# RPi_Extension_contr_sens_conn_board.net
KiCad netlist of a schematic drawn in EAGLE
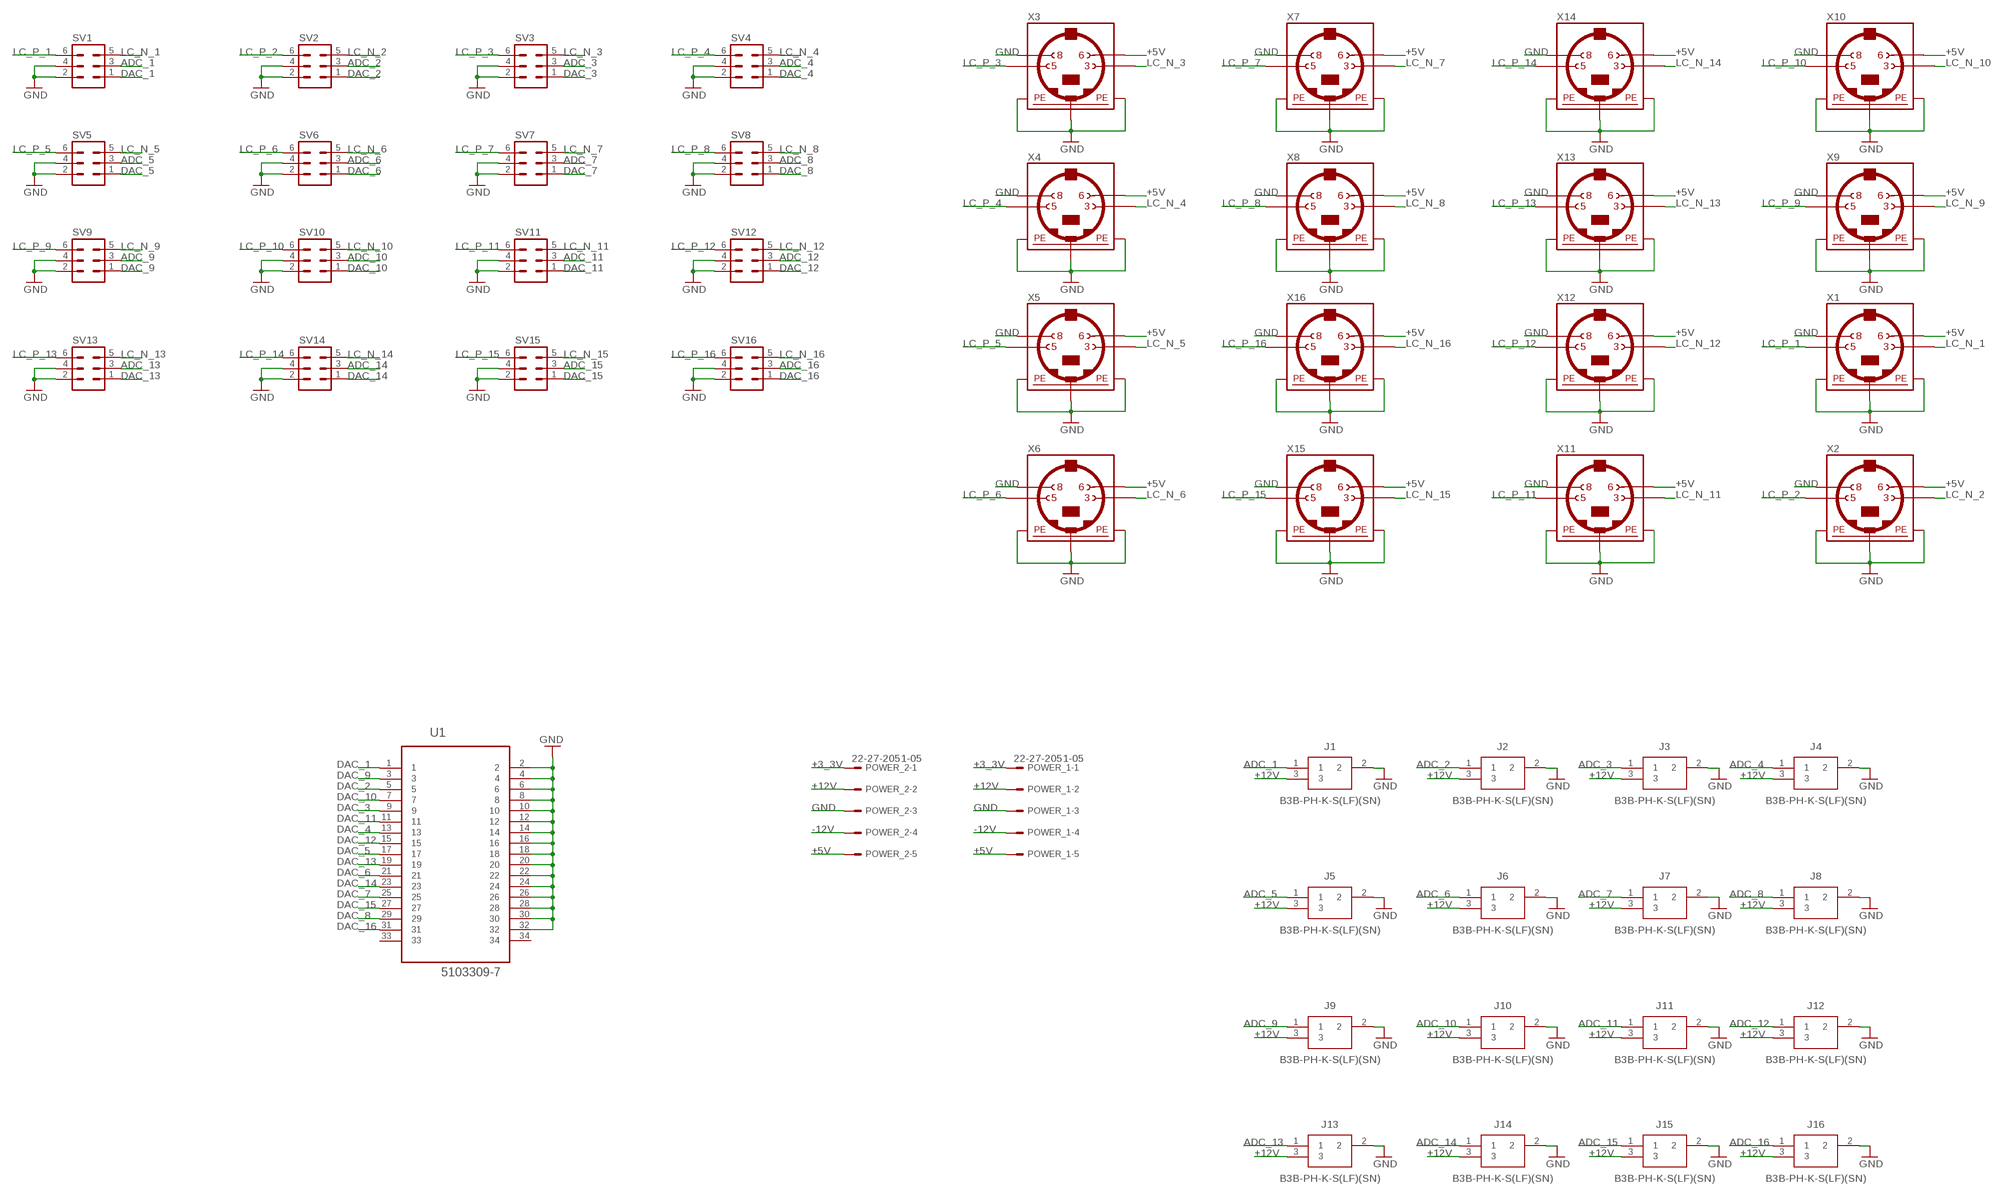
[diagram p0: schematic, sheet 1]

(export (version "E")
  (design (tool "Eeschema 10.0.6"))
  (components
    (comp (ref "J1")
      (value "B3B-PH-K-S(LF)(SN)")
      (footprint "eagle-import:SHDR3W50P0X200_1X3_790X450X600")
      (fields (field (name "RS_PART_NUMBER") "8201431P"))
      (libsource (lib "eagle-import") (part "B3B-PH-K-S(LF)(SN)"))
    )
    (comp (ref "J2")
      (value "B3B-PH-K-S(LF)(SN)")
      (footprint "eagle-import:SHDR3W50P0X200_1X3_790X450X600")
      (fields (field (name "RS_PART_NUMBER") "8201431P"))
      (libsource (lib "eagle-import") (part "B3B-PH-K-S(LF)(SN)"))
    )
    (comp (ref "J3")
      (value "B3B-PH-K-S(LF)(SN)")
      (footprint "eagle-import:SHDR3W50P0X200_1X3_790X450X600")
      (fields (field (name "RS_PART_NUMBER") "8201431P"))
      (libsource (lib "eagle-import") (part "B3B-PH-K-S(LF)(SN)"))
    )
    (comp (ref "J4")
      (value "B3B-PH-K-S(LF)(SN)")
      (footprint "eagle-import:SHDR3W50P0X200_1X3_790X450X600")
      (fields (field (name "RS_PART_NUMBER") "8201431P"))
      (libsource (lib "eagle-import") (part "B3B-PH-K-S(LF)(SN)"))
    )
    (comp (ref "J5")
      (value "B3B-PH-K-S(LF)(SN)")
      (footprint "eagle-import:SHDR3W50P0X200_1X3_790X450X600")
      (fields (field (name "RS_PART_NUMBER") "8201431P"))
      (libsource (lib "eagle-import") (part "B3B-PH-K-S(LF)(SN)"))
    )
    (comp (ref "J6")
      (value "B3B-PH-K-S(LF)(SN)")
      (footprint "eagle-import:SHDR3W50P0X200_1X3_790X450X600")
      (fields (field (name "RS_PART_NUMBER") "8201431P"))
      (libsource (lib "eagle-import") (part "B3B-PH-K-S(LF)(SN)"))
    )
    (comp (ref "J7")
      (value "B3B-PH-K-S(LF)(SN)")
      (footprint "eagle-import:SHDR3W50P0X200_1X3_790X450X600")
      (fields (field (name "RS_PART_NUMBER") "8201431P"))
      (libsource (lib "eagle-import") (part "B3B-PH-K-S(LF)(SN)"))
    )
    (comp (ref "J8")
      (value "B3B-PH-K-S(LF)(SN)")
      (footprint "eagle-import:SHDR3W50P0X200_1X3_790X450X600")
      (fields (field (name "RS_PART_NUMBER") "8201431P"))
      (libsource (lib "eagle-import") (part "B3B-PH-K-S(LF)(SN)"))
    )
    (comp (ref "J9")
      (value "B3B-PH-K-S(LF)(SN)")
      (footprint "eagle-import:SHDR3W50P0X200_1X3_790X450X600")
      (fields (field (name "RS_PART_NUMBER") "8201431P"))
      (libsource (lib "eagle-import") (part "B3B-PH-K-S(LF)(SN)"))
    )
    (comp (ref "J10")
      (value "B3B-PH-K-S(LF)(SN)")
      (footprint "eagle-import:SHDR3W50P0X200_1X3_790X450X600")
      (fields (field (name "RS_PART_NUMBER") "8201431P"))
      (libsource (lib "eagle-import") (part "B3B-PH-K-S(LF)(SN)"))
    )
    (comp (ref "J11")
      (value "B3B-PH-K-S(LF)(SN)")
      (footprint "eagle-import:SHDR3W50P0X200_1X3_790X450X600")
      (fields (field (name "RS_PART_NUMBER") "8201431P"))
      (libsource (lib "eagle-import") (part "B3B-PH-K-S(LF)(SN)"))
    )
    (comp (ref "J12")
      (value "B3B-PH-K-S(LF)(SN)")
      (footprint "eagle-import:SHDR3W50P0X200_1X3_790X450X600")
      (fields (field (name "RS_PART_NUMBER") "8201431P"))
      (libsource (lib "eagle-import") (part "B3B-PH-K-S(LF)(SN)"))
    )
    (comp (ref "J13")
      (value "B3B-PH-K-S(LF)(SN)")
      (footprint "eagle-import:SHDR3W50P0X200_1X3_790X450X600")
      (fields (field (name "RS_PART_NUMBER") "8201431P"))
      (libsource (lib "eagle-import") (part "B3B-PH-K-S(LF)(SN)"))
    )
    (comp (ref "J14")
      (value "B3B-PH-K-S(LF)(SN)")
      (footprint "eagle-import:SHDR3W50P0X200_1X3_790X450X600")
      (fields (field (name "RS_PART_NUMBER") "8201431P"))
      (libsource (lib "eagle-import") (part "B3B-PH-K-S(LF)(SN)"))
    )
    (comp (ref "J15")
      (value "B3B-PH-K-S(LF)(SN)")
      (footprint "eagle-import:SHDR3W50P0X200_1X3_790X450X600")
      (fields (field (name "RS_PART_NUMBER") "8201431P"))
      (libsource (lib "eagle-import") (part "B3B-PH-K-S(LF)(SN)"))
    )
    (comp (ref "J16")
      (value "B3B-PH-K-S(LF)(SN)")
      (footprint "eagle-import:SHDR3W50P0X200_1X3_790X450X600")
      (fields (field (name "RS_PART_NUMBER") "8201431P"))
      (libsource (lib "eagle-import") (part "B3B-PH-K-S(LF)(SN)"))
    )
    (comp (ref "POWER_1")
      (value "22-27-2051-05")
      (footprint "eagle-import:6410-05")
      (libsource (lib "eagle-import") (part "22-?-0527-2051"))
    )
    (comp (ref "POWER_2")
      (value "22-27-2051-05")
      (footprint "eagle-import:6410-05")
      (libsource (lib "eagle-import") (part "22-?-0527-2051"))
    )
    (comp (ref "SV1")
      (value "MA03-2")
      (footprint "eagle-import:MA03-2")
      (libsource (lib "eagle-import") (part "MA03-2"))
    )
    (comp (ref "SV2")
      (value "MA03-2")
      (footprint "eagle-import:MA03-2")
      (libsource (lib "eagle-import") (part "MA03-2"))
    )
    (comp (ref "SV3")
      (value "MA03-2")
      (footprint "eagle-import:MA03-2")
      (libsource (lib "eagle-import") (part "MA03-2"))
    )
    (comp (ref "SV4")
      (value "MA03-2")
      (footprint "eagle-import:MA03-2")
      (libsource (lib "eagle-import") (part "MA03-2"))
    )
    (comp (ref "SV5")
      (value "MA03-2")
      (footprint "eagle-import:MA03-2")
      (libsource (lib "eagle-import") (part "MA03-2"))
    )
    (comp (ref "SV6")
      (value "MA03-2")
      (footprint "eagle-import:MA03-2")
      (libsource (lib "eagle-import") (part "MA03-2"))
    )
    (comp (ref "SV7")
      (value "MA03-2")
      (footprint "eagle-import:MA03-2")
      (libsource (lib "eagle-import") (part "MA03-2"))
    )
    (comp (ref "SV8")
      (value "MA03-2")
      (footprint "eagle-import:MA03-2")
      (libsource (lib "eagle-import") (part "MA03-2"))
    )
    (comp (ref "SV9")
      (value "MA03-2")
      (footprint "eagle-import:MA03-2")
      (libsource (lib "eagle-import") (part "MA03-2"))
    )
    (comp (ref "SV10")
      (value "MA03-2")
      (footprint "eagle-import:MA03-2")
      (libsource (lib "eagle-import") (part "MA03-2"))
    )
    (comp (ref "SV11")
      (value "MA03-2")
      (footprint "eagle-import:MA03-2")
      (libsource (lib "eagle-import") (part "MA03-2"))
    )
    (comp (ref "SV12")
      (value "MA03-2")
      (footprint "eagle-import:MA03-2")
      (libsource (lib "eagle-import") (part "MA03-2"))
    )
    (comp (ref "SV13")
      (value "MA03-2")
      (footprint "eagle-import:MA03-2")
      (libsource (lib "eagle-import") (part "MA03-2"))
    )
    (comp (ref "SV14")
      (value "MA03-2")
      (footprint "eagle-import:MA03-2")
      (libsource (lib "eagle-import") (part "MA03-2"))
    )
    (comp (ref "SV15")
      (value "MA03-2")
      (footprint "eagle-import:MA03-2")
      (libsource (lib "eagle-import") (part "MA03-2"))
    )
    (comp (ref "SV16")
      (value "MA03-2")
      (footprint "eagle-import:MA03-2")
      (libsource (lib "eagle-import") (part "MA03-2"))
    )
    (comp (ref "U1")
      (value "5103309-7")
      (footprint "eagle-import:TYCO_5103309-7")
      (libsource (lib "eagle-import") (part "5103309-7"))
    )
    (comp (ref "X1")
      (value "MINI_DIN_4")
      (footprint "eagle-import:M_DIN4")
      (libsource (lib "eagle-import") (part "MINI_DIN_4"))
    )
    (comp (ref "X2")
      (value "MINI_DIN_4")
      (footprint "eagle-import:M_DIN4")
      (libsource (lib "eagle-import") (part "MINI_DIN_4"))
    )
    (comp (ref "X3")
      (value "MINI_DIN_4")
      (footprint "eagle-import:M_DIN4")
      (libsource (lib "eagle-import") (part "MINI_DIN_4"))
    )
    (comp (ref "X4")
      (value "MINI_DIN_4")
      (footprint "eagle-import:M_DIN4")
      (libsource (lib "eagle-import") (part "MINI_DIN_4"))
    )
    (comp (ref "X5")
      (value "MINI_DIN_4")
      (footprint "eagle-import:M_DIN4")
      (libsource (lib "eagle-import") (part "MINI_DIN_4"))
    )
    (comp (ref "X6")
      (value "MINI_DIN_4")
      (footprint "eagle-import:M_DIN4")
      (libsource (lib "eagle-import") (part "MINI_DIN_4"))
    )
    (comp (ref "X7")
      (value "MINI_DIN_4")
      (footprint "eagle-import:M_DIN4")
      (libsource (lib "eagle-import") (part "MINI_DIN_4"))
    )
    (comp (ref "X8")
      (value "MINI_DIN_4")
      (footprint "eagle-import:M_DIN4")
      (libsource (lib "eagle-import") (part "MINI_DIN_4"))
    )
    (comp (ref "X9")
      (value "MINI_DIN_4")
      (footprint "eagle-import:M_DIN4")
      (libsource (lib "eagle-import") (part "MINI_DIN_4"))
    )
    (comp (ref "X10")
      (value "MINI_DIN_4")
      (footprint "eagle-import:M_DIN4")
      (libsource (lib "eagle-import") (part "MINI_DIN_4"))
    )
    (comp (ref "X11")
      (value "MINI_DIN_4")
      (footprint "eagle-import:M_DIN4")
      (libsource (lib "eagle-import") (part "MINI_DIN_4"))
    )
    (comp (ref "X12")
      (value "MINI_DIN_4")
      (footprint "eagle-import:M_DIN4")
      (libsource (lib "eagle-import") (part "MINI_DIN_4"))
    )
    (comp (ref "X13")
      (value "MINI_DIN_4")
      (footprint "eagle-import:M_DIN4")
      (libsource (lib "eagle-import") (part "MINI_DIN_4"))
    )
    (comp (ref "X14")
      (value "MINI_DIN_4")
      (footprint "eagle-import:M_DIN4")
      (libsource (lib "eagle-import") (part "MINI_DIN_4"))
    )
    (comp (ref "X15")
      (value "MINI_DIN_4")
      (footprint "eagle-import:M_DIN4")
      (libsource (lib "eagle-import") (part "MINI_DIN_4"))
    )
    (comp (ref "X16")
      (value "MINI_DIN_4")
      (footprint "eagle-import:M_DIN4")
      (libsource (lib "eagle-import") (part "MINI_DIN_4"))
    )
  )
  (nets
    (net (code "1") (name "/+3_3V") (class "Default")
      (node (ref "POWER_1") (pin "1") (pinfunction "S_1") (pintype "passive"))
      (node (ref "POWER_2") (pin "1") (pinfunction "S_1") (pintype "passive"))
    )
    (net (code "2") (name "/+5V") (class "Default")
      (node (ref "POWER_1") (pin "5") (pinfunction "S_5") (pintype "passive"))
      (node (ref "POWER_2") (pin "5") (pinfunction "S_5") (pintype "passive"))
      (node (ref "X1") (pin "6") (pinfunction "6_6") (pintype "passive"))
      (node (ref "X10") (pin "6") (pinfunction "6_6") (pintype "passive"))
      (node (ref "X11") (pin "6") (pinfunction "6_6") (pintype "passive"))
      (node (ref "X12") (pin "6") (pinfunction "6_6") (pintype "passive"))
      (node (ref "X13") (pin "6") (pinfunction "6_6") (pintype "passive"))
      (node (ref "X14") (pin "6") (pinfunction "6_6") (pintype "passive"))
      (node (ref "X15") (pin "6") (pinfunction "6_6") (pintype "passive"))
      (node (ref "X16") (pin "6") (pinfunction "6_6") (pintype "passive"))
      (node (ref "X2") (pin "6") (pinfunction "6_6") (pintype "passive"))
      (node (ref "X3") (pin "6") (pinfunction "6_6") (pintype "passive"))
      (node (ref "X4") (pin "6") (pinfunction "6_6") (pintype "passive"))
      (node (ref "X5") (pin "6") (pinfunction "6_6") (pintype "passive"))
      (node (ref "X6") (pin "6") (pinfunction "6_6") (pintype "passive"))
      (node (ref "X7") (pin "6") (pinfunction "6_6") (pintype "passive"))
      (node (ref "X8") (pin "6") (pinfunction "6_6") (pintype "passive"))
      (node (ref "X9") (pin "6") (pinfunction "6_6") (pintype "passive"))
    )
    (net (code "3") (name "/+12V") (class "Default")
      (node (ref "J1") (pin "3") (pinfunction "3_3") (pintype "input"))
      (node (ref "J10") (pin "3") (pinfunction "3_3") (pintype "input"))
      (node (ref "J11") (pin "3") (pinfunction "3_3") (pintype "input"))
      (node (ref "J12") (pin "3") (pinfunction "3_3") (pintype "input"))
      (node (ref "J13") (pin "3") (pinfunction "3_3") (pintype "input"))
      (node (ref "J14") (pin "3") (pinfunction "3_3") (pintype "input"))
      (node (ref "J15") (pin "3") (pinfunction "3_3") (pintype "input"))
      (node (ref "J16") (pin "3") (pinfunction "3_3") (pintype "input"))
      (node (ref "J2") (pin "3") (pinfunction "3_3") (pintype "input"))
      (node (ref "J3") (pin "3") (pinfunction "3_3") (pintype "input"))
      (node (ref "J4") (pin "3") (pinfunction "3_3") (pintype "input"))
      (node (ref "J5") (pin "3") (pinfunction "3_3") (pintype "input"))
      (node (ref "J6") (pin "3") (pinfunction "3_3") (pintype "input"))
      (node (ref "J7") (pin "3") (pinfunction "3_3") (pintype "input"))
      (node (ref "J8") (pin "3") (pinfunction "3_3") (pintype "input"))
      (node (ref "J9") (pin "3") (pinfunction "3_3") (pintype "input"))
      (node (ref "POWER_1") (pin "2") (pinfunction "S_2") (pintype "passive"))
      (node (ref "POWER_2") (pin "2") (pinfunction "S_2") (pintype "passive"))
    )
    (net (code "4") (name "/-12V") (class "Default")
      (node (ref "POWER_1") (pin "4") (pinfunction "S_4") (pintype "passive"))
      (node (ref "POWER_2") (pin "4") (pinfunction "S_4") (pintype "passive"))
    )
    (net (code "5") (name "/ADC_1") (class "Default")
      (node (ref "J1") (pin "1") (pinfunction "1_1") (pintype "input"))
      (node (ref "SV1") (pin "3") (pinfunction "3_3") (pintype "passive"))
    )
    (net (code "6") (name "/ADC_2") (class "Default")
      (node (ref "J2") (pin "1") (pinfunction "1_1") (pintype "input"))
      (node (ref "SV2") (pin "3") (pinfunction "3_3") (pintype "passive"))
    )
    (net (code "7") (name "/ADC_3") (class "Default")
      (node (ref "J3") (pin "1") (pinfunction "1_1") (pintype "input"))
      (node (ref "SV3") (pin "3") (pinfunction "3_3") (pintype "passive"))
    )
    (net (code "8") (name "/ADC_4") (class "Default")
      (node (ref "J4") (pin "1") (pinfunction "1_1") (pintype "input"))
      (node (ref "SV4") (pin "3") (pinfunction "3_3") (pintype "passive"))
    )
    (net (code "9") (name "/ADC_5") (class "Default")
      (node (ref "J5") (pin "1") (pinfunction "1_1") (pintype "input"))
      (node (ref "SV5") (pin "3") (pinfunction "3_3") (pintype "passive"))
    )
    (net (code "10") (name "/ADC_6") (class "Default")
      (node (ref "J6") (pin "1") (pinfunction "1_1") (pintype "input"))
      (node (ref "SV6") (pin "3") (pinfunction "3_3") (pintype "passive"))
    )
    (net (code "11") (name "/ADC_7") (class "Default")
      (node (ref "J7") (pin "1") (pinfunction "1_1") (pintype "input"))
      (node (ref "SV7") (pin "3") (pinfunction "3_3") (pintype "passive"))
    )
    (net (code "12") (name "/ADC_8") (class "Default")
      (node (ref "J8") (pin "1") (pinfunction "1_1") (pintype "input"))
      (node (ref "SV8") (pin "3") (pinfunction "3_3") (pintype "passive"))
    )
    (net (code "13") (name "/ADC_9") (class "Default")
      (node (ref "J9") (pin "1") (pinfunction "1_1") (pintype "input"))
      (node (ref "SV9") (pin "3") (pinfunction "3_3") (pintype "passive"))
    )
    (net (code "14") (name "/ADC_10") (class "Default")
      (node (ref "J10") (pin "1") (pinfunction "1_1") (pintype "input"))
      (node (ref "SV10") (pin "3") (pinfunction "3_3") (pintype "passive"))
    )
    (net (code "15") (name "/ADC_11") (class "Default")
      (node (ref "J11") (pin "1") (pinfunction "1_1") (pintype "input"))
      (node (ref "SV11") (pin "3") (pinfunction "3_3") (pintype "passive"))
    )
    (net (code "16") (name "/ADC_12") (class "Default")
      (node (ref "J12") (pin "1") (pinfunction "1_1") (pintype "input"))
      (node (ref "SV12") (pin "3") (pinfunction "3_3") (pintype "passive"))
    )
    (net (code "17") (name "/ADC_13") (class "Default")
      (node (ref "J13") (pin "1") (pinfunction "1_1") (pintype "input"))
      (node (ref "SV13") (pin "3") (pinfunction "3_3") (pintype "passive"))
    )
    (net (code "18") (name "/ADC_14") (class "Default")
      (node (ref "J14") (pin "1") (pinfunction "1_1") (pintype "input"))
      (node (ref "SV14") (pin "3") (pinfunction "3_3") (pintype "passive"))
    )
    (net (code "19") (name "/ADC_15") (class "Default")
      (node (ref "J15") (pin "1") (pinfunction "1_1") (pintype "input"))
      (node (ref "SV15") (pin "3") (pinfunction "3_3") (pintype "passive"))
    )
    (net (code "20") (name "/ADC_16") (class "Default")
      (node (ref "J16") (pin "1") (pinfunction "1_1") (pintype "input"))
      (node (ref "SV16") (pin "3") (pinfunction "3_3") (pintype "passive"))
    )
    (net (code "21") (name "/DAC_1") (class "Default")
      (node (ref "SV1") (pin "1") (pinfunction "1_1") (pintype "passive"))
      (node (ref "U1") (pin "1") (pinfunction "1_1") (pintype "passive"))
    )
    (net (code "22") (name "/DAC_2") (class "Default")
      (node (ref "SV2") (pin "1") (pinfunction "1_1") (pintype "passive"))
      (node (ref "U1") (pin "5") (pinfunction "5_5") (pintype "passive"))
    )
    (net (code "23") (name "/DAC_3") (class "Default")
      (node (ref "SV3") (pin "1") (pinfunction "1_1") (pintype "passive"))
      (node (ref "U1") (pin "9") (pinfunction "9_9") (pintype "passive"))
    )
    (net (code "24") (name "/DAC_4") (class "Default")
      (node (ref "SV4") (pin "1") (pinfunction "1_1") (pintype "passive"))
      (node (ref "U1") (pin "13") (pinfunction "13_13") (pintype "passive"))
    )
    (net (code "25") (name "/DAC_5") (class "Default")
      (node (ref "SV5") (pin "1") (pinfunction "1_1") (pintype "passive"))
      (node (ref "U1") (pin "17") (pinfunction "17_17") (pintype "passive"))
    )
    (net (code "26") (name "/DAC_6") (class "Default")
      (node (ref "SV6") (pin "1") (pinfunction "1_1") (pintype "passive"))
      (node (ref "U1") (pin "21") (pinfunction "21_21") (pintype "passive"))
    )
    (net (code "27") (name "/DAC_7") (class "Default")
      (node (ref "SV7") (pin "1") (pinfunction "1_1") (pintype "passive"))
      (node (ref "U1") (pin "25") (pinfunction "25_25") (pintype "passive"))
    )
    (net (code "28") (name "/DAC_8") (class "Default")
      (node (ref "SV8") (pin "1") (pinfunction "1_1") (pintype "passive"))
      (node (ref "U1") (pin "29") (pinfunction "29_29") (pintype "passive"))
    )
    (net (code "29") (name "/DAC_9") (class "Default")
      (node (ref "SV9") (pin "1") (pinfunction "1_1") (pintype "passive"))
      (node (ref "U1") (pin "3") (pinfunction "3_3") (pintype "passive"))
    )
    (net (code "30") (name "/DAC_10") (class "Default")
      (node (ref "SV10") (pin "1") (pinfunction "1_1") (pintype "passive"))
      (node (ref "U1") (pin "7") (pinfunction "7_7") (pintype "passive"))
    )
    (net (code "31") (name "/DAC_11") (class "Default")
      (node (ref "SV11") (pin "1") (pinfunction "1_1") (pintype "passive"))
      (node (ref "U1") (pin "11") (pinfunction "11_11") (pintype "passive"))
    )
    (net (code "32") (name "/DAC_12") (class "Default")
      (node (ref "SV12") (pin "1") (pinfunction "1_1") (pintype "passive"))
      (node (ref "U1") (pin "15") (pinfunction "15_15") (pintype "passive"))
    )
    (net (code "33") (name "/DAC_13") (class "Default")
      (node (ref "SV13") (pin "1") (pinfunction "1_1") (pintype "passive"))
      (node (ref "U1") (pin "19") (pinfunction "19_19") (pintype "passive"))
    )
    (net (code "34") (name "/DAC_14") (class "Default")
      (node (ref "SV14") (pin "1") (pinfunction "1_1") (pintype "passive"))
      (node (ref "U1") (pin "23") (pinfunction "23_23") (pintype "passive"))
    )
    (net (code "35") (name "/DAC_15") (class "Default")
      (node (ref "SV15") (pin "1") (pinfunction "1_1") (pintype "passive"))
      (node (ref "U1") (pin "27") (pinfunction "27_27") (pintype "passive"))
    )
    (net (code "36") (name "/DAC_16") (class "Default")
      (node (ref "SV16") (pin "1") (pinfunction "1_1") (pintype "passive"))
      (node (ref "U1") (pin "31") (pinfunction "31_31") (pintype "passive"))
    )
    (net (code "37") (name "/LC_N_1") (class "Default")
      (node (ref "SV1") (pin "5") (pinfunction "5_5") (pintype "passive"))
      (node (ref "X1") (pin "3") (pinfunction "3_3") (pintype "passive"))
    )
    (net (code "38") (name "/LC_N_2") (class "Default")
      (node (ref "SV2") (pin "5") (pinfunction "5_5") (pintype "passive"))
      (node (ref "X2") (pin "3") (pinfunction "3_3") (pintype "passive"))
    )
    (net (code "39") (name "/LC_N_3") (class "Default")
      (node (ref "SV3") (pin "5") (pinfunction "5_5") (pintype "passive"))
      (node (ref "X3") (pin "3") (pinfunction "3_3") (pintype "passive"))
    )
    (net (code "40") (name "/LC_N_4") (class "Default")
      (node (ref "SV4") (pin "5") (pinfunction "5_5") (pintype "passive"))
      (node (ref "X4") (pin "3") (pinfunction "3_3") (pintype "passive"))
    )
    (net (code "41") (name "/LC_N_5") (class "Default")
      (node (ref "SV5") (pin "5") (pinfunction "5_5") (pintype "passive"))
      (node (ref "X5") (pin "3") (pinfunction "3_3") (pintype "passive"))
    )
    (net (code "42") (name "/LC_N_6") (class "Default")
      (node (ref "SV6") (pin "5") (pinfunction "5_5") (pintype "passive"))
      (node (ref "X6") (pin "3") (pinfunction "3_3") (pintype "passive"))
    )
    (net (code "43") (name "/LC_N_7") (class "Default")
      (node (ref "SV7") (pin "5") (pinfunction "5_5") (pintype "passive"))
      (node (ref "X7") (pin "3") (pinfunction "3_3") (pintype "passive"))
    )
    (net (code "44") (name "/LC_N_8") (class "Default")
      (node (ref "SV8") (pin "5") (pinfunction "5_5") (pintype "passive"))
      (node (ref "X8") (pin "3") (pinfunction "3_3") (pintype "passive"))
    )
    (net (code "45") (name "/LC_N_9") (class "Default")
      (node (ref "SV9") (pin "5") (pinfunction "5_5") (pintype "passive"))
      (node (ref "X9") (pin "3") (pinfunction "3_3") (pintype "passive"))
    )
    (net (code "46") (name "/LC_N_10") (class "Default")
      (node (ref "SV10") (pin "5") (pinfunction "5_5") (pintype "passive"))
      (node (ref "X10") (pin "3") (pinfunction "3_3") (pintype "passive"))
    )
    (net (code "47") (name "/LC_N_11") (class "Default")
      (node (ref "SV11") (pin "5") (pinfunction "5_5") (pintype "passive"))
      (node (ref "X11") (pin "3") (pinfunction "3_3") (pintype "passive"))
    )
    (net (code "48") (name "/LC_N_12") (class "Default")
      (node (ref "SV12") (pin "5") (pinfunction "5_5") (pintype "passive"))
      (node (ref "X12") (pin "3") (pinfunction "3_3") (pintype "passive"))
    )
    (net (code "49") (name "/LC_N_13") (class "Default")
      (node (ref "SV13") (pin "5") (pinfunction "5_5") (pintype "passive"))
      (node (ref "X13") (pin "3") (pinfunction "3_3") (pintype "passive"))
    )
    (net (code "50") (name "/LC_N_14") (class "Default")
      (node (ref "SV14") (pin "5") (pinfunction "5_5") (pintype "passive"))
      (node (ref "X14") (pin "3") (pinfunction "3_3") (pintype "passive"))
    )
    (net (code "51") (name "/LC_N_15") (class "Default")
      (node (ref "SV15") (pin "5") (pinfunction "5_5") (pintype "passive"))
      (node (ref "X15") (pin "3") (pinfunction "3_3") (pintype "passive"))
    )
    (net (code "52") (name "/LC_N_16") (class "Default")
      (node (ref "SV16") (pin "5") (pinfunction "5_5") (pintype "passive"))
      (node (ref "X16") (pin "3") (pinfunction "3_3") (pintype "passive"))
    )
    (net (code "53") (name "/LC_P_1") (class "Default")
      (node (ref "SV1") (pin "6") (pinfunction "6_6") (pintype "passive"))
      (node (ref "X1") (pin "5") (pinfunction "5_5") (pintype "passive"))
    )
    (net (code "54") (name "/LC_P_2") (class "Default")
      (node (ref "SV2") (pin "6") (pinfunction "6_6") (pintype "passive"))
      (node (ref "X2") (pin "5") (pinfunction "5_5") (pintype "passive"))
    )
    (net (code "55") (name "/LC_P_3") (class "Default")
      (node (ref "SV3") (pin "6") (pinfunction "6_6") (pintype "passive"))
      (node (ref "X3") (pin "5") (pinfunction "5_5") (pintype "passive"))
    )
    (net (code "56") (name "/LC_P_4") (class "Default")
      (node (ref "SV4") (pin "6") (pinfunction "6_6") (pintype "passive"))
      (node (ref "X4") (pin "5") (pinfunction "5_5") (pintype "passive"))
    )
    (net (code "57") (name "/LC_P_5") (class "Default")
      (node (ref "SV5") (pin "6") (pinfunction "6_6") (pintype "passive"))
      (node (ref "X5") (pin "5") (pinfunction "5_5") (pintype "passive"))
    )
    (net (code "58") (name "/LC_P_6") (class "Default")
      (node (ref "SV6") (pin "6") (pinfunction "6_6") (pintype "passive"))
      (node (ref "X6") (pin "5") (pinfunction "5_5") (pintype "passive"))
    )
    (net (code "59") (name "/LC_P_7") (class "Default")
      (node (ref "SV7") (pin "6") (pinfunction "6_6") (pintype "passive"))
      (node (ref "X7") (pin "5") (pinfunction "5_5") (pintype "passive"))
    )
    (net (code "60") (name "/LC_P_8") (class "Default")
      (node (ref "SV8") (pin "6") (pinfunction "6_6") (pintype "passive"))
      (node (ref "X8") (pin "5") (pinfunction "5_5") (pintype "passive"))
    )
    (net (code "61") (name "/LC_P_9") (class "Default")
      (node (ref "SV9") (pin "6") (pinfunction "6_6") (pintype "passive"))
      (node (ref "X9") (pin "5") (pinfunction "5_5") (pintype "passive"))
    )
    (net (code "62") (name "/LC_P_10") (class "Default")
      (node (ref "SV10") (pin "6") (pinfunction "6_6") (pintype "passive"))
      (node (ref "X10") (pin "5") (pinfunction "5_5") (pintype "passive"))
    )
    (net (code "63") (name "/LC_P_11") (class "Default")
      (node (ref "SV11") (pin "6") (pinfunction "6_6") (pintype "passive"))
      (node (ref "X11") (pin "5") (pinfunction "5_5") (pintype "passive"))
    )
    (net (code "64") (name "/LC_P_12") (class "Default")
      (node (ref "SV12") (pin "6") (pinfunction "6_6") (pintype "passive"))
      (node (ref "X12") (pin "5") (pinfunction "5_5") (pintype "passive"))
    )
    (net (code "65") (name "/LC_P_13") (class "Default")
      (node (ref "SV13") (pin "6") (pinfunction "6_6") (pintype "passive"))
      (node (ref "X13") (pin "5") (pinfunction "5_5") (pintype "passive"))
    )
    (net (code "66") (name "/LC_P_14") (class "Default")
      (node (ref "SV14") (pin "6") (pinfunction "6_6") (pintype "passive"))
      (node (ref "X14") (pin "5") (pinfunction "5_5") (pintype "passive"))
    )
    (net (code "67") (name "/LC_P_15") (class "Default")
      (node (ref "SV15") (pin "6") (pinfunction "6_6") (pintype "passive"))
      (node (ref "X15") (pin "5") (pinfunction "5_5") (pintype "passive"))
    )
    (net (code "68") (name "/LC_P_16") (class "Default")
      (node (ref "SV16") (pin "6") (pinfunction "6_6") (pintype "passive"))
      (node (ref "X16") (pin "5") (pinfunction "5_5") (pintype "passive"))
    )
    (net (code "69") (name "GND") (class "Default")
      (node (ref "J1") (pin "2") (pinfunction "2_2") (pintype "input"))
      (node (ref "J10") (pin "2") (pinfunction "2_2") (pintype "input"))
      (node (ref "J11") (pin "2") (pinfunction "2_2") (pintype "input"))
      (node (ref "J12") (pin "2") (pinfunction "2_2") (pintype "input"))
      (node (ref "J13") (pin "2") (pinfunction "2_2") (pintype "input"))
      (node (ref "J14") (pin "2") (pinfunction "2_2") (pintype "input"))
      (node (ref "J15") (pin "2") (pinfunction "2_2") (pintype "input"))
      (node (ref "J16") (pin "2") (pinfunction "2_2") (pintype "input"))
      (node (ref "J2") (pin "2") (pinfunction "2_2") (pintype "input"))
      (node (ref "J3") (pin "2") (pinfunction "2_2") (pintype "input"))
      (node (ref "J4") (pin "2") (pinfunction "2_2") (pintype "input"))
      (node (ref "J5") (pin "2") (pinfunction "2_2") (pintype "input"))
      (node (ref "J6") (pin "2") (pinfunction "2_2") (pintype "input"))
      (node (ref "J7") (pin "2") (pinfunction "2_2") (pintype "input"))
      (node (ref "J8") (pin "2") (pinfunction "2_2") (pintype "input"))
      (node (ref "J9") (pin "2") (pinfunction "2_2") (pintype "input"))
      (node (ref "POWER_1") (pin "3") (pinfunction "S_3") (pintype "passive"))
      (node (ref "POWER_2") (pin "3") (pinfunction "S_3") (pintype "passive"))
      (node (ref "SV1") (pin "2") (pinfunction "2_2") (pintype "passive"))
      (node (ref "SV1") (pin "4") (pinfunction "4_4") (pintype "passive"))
      (node (ref "SV10") (pin "2") (pinfunction "2_2") (pintype "passive"))
      (node (ref "SV10") (pin "4") (pinfunction "4_4") (pintype "passive"))
      (node (ref "SV11") (pin "2") (pinfunction "2_2") (pintype "passive"))
      (node (ref "SV11") (pin "4") (pinfunction "4_4") (pintype "passive"))
      (node (ref "SV12") (pin "2") (pinfunction "2_2") (pintype "passive"))
      (node (ref "SV12") (pin "4") (pinfunction "4_4") (pintype "passive"))
      (node (ref "SV13") (pin "2") (pinfunction "2_2") (pintype "passive"))
      (node (ref "SV13") (pin "4") (pinfunction "4_4") (pintype "passive"))
      (node (ref "SV14") (pin "2") (pinfunction "2_2") (pintype "passive"))
      (node (ref "SV14") (pin "4") (pinfunction "4_4") (pintype "passive"))
      (node (ref "SV15") (pin "2") (pinfunction "2_2") (pintype "passive"))
      (node (ref "SV15") (pin "4") (pinfunction "4_4") (pintype "passive"))
      (node (ref "SV16") (pin "2") (pinfunction "2_2") (pintype "passive"))
      (node (ref "SV16") (pin "4") (pinfunction "4_4") (pintype "passive"))
      (node (ref "SV2") (pin "2") (pinfunction "2_2") (pintype "passive"))
      (node (ref "SV2") (pin "4") (pinfunction "4_4") (pintype "passive"))
      (node (ref "SV3") (pin "2") (pinfunction "2_2") (pintype "passive"))
      (node (ref "SV3") (pin "4") (pinfunction "4_4") (pintype "passive"))
      (node (ref "SV4") (pin "2") (pinfunction "2_2") (pintype "passive"))
      (node (ref "SV4") (pin "4") (pinfunction "4_4") (pintype "passive"))
      (node (ref "SV5") (pin "2") (pinfunction "2_2") (pintype "passive"))
      (node (ref "SV5") (pin "4") (pinfunction "4_4") (pintype "passive"))
      (node (ref "SV6") (pin "2") (pinfunction "2_2") (pintype "passive"))
      (node (ref "SV6") (pin "4") (pinfunction "4_4") (pintype "passive"))
      (node (ref "SV7") (pin "2") (pinfunction "2_2") (pintype "passive"))
      (node (ref "SV7") (pin "4") (pinfunction "4_4") (pintype "passive"))
      (node (ref "SV8") (pin "2") (pinfunction "2_2") (pintype "passive"))
      (node (ref "SV8") (pin "4") (pinfunction "4_4") (pintype "passive"))
      (node (ref "SV9") (pin "2") (pinfunction "2_2") (pintype "passive"))
      (node (ref "SV9") (pin "4") (pinfunction "4_4") (pintype "passive"))
      (node (ref "U1") (pin "10") (pinfunction "10_10") (pintype "passive"))
      (node (ref "U1") (pin "12") (pinfunction "12_12") (pintype "passive"))
      (node (ref "U1") (pin "14") (pinfunction "14_14") (pintype "passive"))
      (node (ref "U1") (pin "16") (pinfunction "16_16") (pintype "passive"))
      (node (ref "U1") (pin "18") (pinfunction "18_18") (pintype "passive"))
      (node (ref "U1") (pin "2") (pinfunction "2_2") (pintype "passive"))
      (node (ref "U1") (pin "20") (pinfunction "20_20") (pintype "passive"))
      (node (ref "U1") (pin "22") (pinfunction "22_22") (pintype "passive"))
      (node (ref "U1") (pin "24") (pinfunction "24_24") (pintype "passive"))
      (node (ref "U1") (pin "26") (pinfunction "26_26") (pintype "passive"))
      (node (ref "U1") (pin "28") (pinfunction "28_28") (pintype "passive"))
      (node (ref "U1") (pin "30") (pinfunction "30_30") (pintype "passive"))
      (node (ref "U1") (pin "32") (pinfunction "32_32") (pintype "passive"))
      (node (ref "U1") (pin "4") (pinfunction "4_4") (pintype "passive"))
      (node (ref "U1") (pin "6") (pinfunction "6_6") (pintype "passive"))
      (node (ref "U1") (pin "8") (pinfunction "8_8") (pintype "passive"))
      (node (ref "X1") (pin "8") (pinfunction "8_8") (pintype "passive"))
      (node (ref "X1") (pin "SH1") (pinfunction "PE1_SH1") (pintype "power_in"))
      (node (ref "X1") (pin "SH2") (pinfunction "PE2_SH2") (pintype "power_in"))
      (node (ref "X1") (pin "SH3") (pinfunction "PE3_SH3") (pintype "power_in"))
      (node (ref "X10") (pin "8") (pinfunction "8_8") (pintype "passive"))
      (node (ref "X10") (pin "SH1") (pinfunction "PE1_SH1") (pintype "power_in"))
      (node (ref "X10") (pin "SH2") (pinfunction "PE2_SH2") (pintype "power_in"))
      (node (ref "X10") (pin "SH3") (pinfunction "PE3_SH3") (pintype "power_in"))
      (node (ref "X11") (pin "8") (pinfunction "8_8") (pintype "passive"))
      (node (ref "X11") (pin "SH1") (pinfunction "PE1_SH1") (pintype "power_in"))
      (node (ref "X11") (pin "SH2") (pinfunction "PE2_SH2") (pintype "power_in"))
      (node (ref "X11") (pin "SH3") (pinfunction "PE3_SH3") (pintype "power_in"))
      (node (ref "X12") (pin "8") (pinfunction "8_8") (pintype "passive"))
      (node (ref "X12") (pin "SH1") (pinfunction "PE1_SH1") (pintype "power_in"))
      (node (ref "X12") (pin "SH2") (pinfunction "PE2_SH2") (pintype "power_in"))
      (node (ref "X12") (pin "SH3") (pinfunction "PE3_SH3") (pintype "power_in"))
      (node (ref "X13") (pin "8") (pinfunction "8_8") (pintype "passive"))
      (node (ref "X13") (pin "SH1") (pinfunction "PE1_SH1") (pintype "power_in"))
      (node (ref "X13") (pin "SH2") (pinfunction "PE2_SH2") (pintype "power_in"))
      (node (ref "X13") (pin "SH3") (pinfunction "PE3_SH3") (pintype "power_in"))
      (node (ref "X14") (pin "8") (pinfunction "8_8") (pintype "passive"))
      (node (ref "X14") (pin "SH1") (pinfunction "PE1_SH1") (pintype "power_in"))
      (node (ref "X14") (pin "SH2") (pinfunction "PE2_SH2") (pintype "power_in"))
      (node (ref "X14") (pin "SH3") (pinfunction "PE3_SH3") (pintype "power_in"))
      (node (ref "X15") (pin "8") (pinfunction "8_8") (pintype "passive"))
      (node (ref "X15") (pin "SH1") (pinfunction "PE1_SH1") (pintype "power_in"))
      (node (ref "X15") (pin "SH2") (pinfunction "PE2_SH2") (pintype "power_in"))
      (node (ref "X15") (pin "SH3") (pinfunction "PE3_SH3") (pintype "power_in"))
      (node (ref "X16") (pin "8") (pinfunction "8_8") (pintype "passive"))
      (node (ref "X16") (pin "SH1") (pinfunction "PE1_SH1") (pintype "power_in"))
      (node (ref "X16") (pin "SH2") (pinfunction "PE2_SH2") (pintype "power_in"))
      (node (ref "X16") (pin "SH3") (pinfunction "PE3_SH3") (pintype "power_in"))
      (node (ref "X2") (pin "8") (pinfunction "8_8") (pintype "passive"))
      (node (ref "X2") (pin "SH1") (pinfunction "PE1_SH1") (pintype "power_in"))
      (node (ref "X2") (pin "SH2") (pinfunction "PE2_SH2") (pintype "power_in"))
      (node (ref "X2") (pin "SH3") (pinfunction "PE3_SH3") (pintype "power_in"))
      (node (ref "X3") (pin "8") (pinfunction "8_8") (pintype "passive"))
      (node (ref "X3") (pin "SH1") (pinfunction "PE1_SH1") (pintype "power_in"))
      (node (ref "X3") (pin "SH2") (pinfunction "PE2_SH2") (pintype "power_in"))
      (node (ref "X3") (pin "SH3") (pinfunction "PE3_SH3") (pintype "power_in"))
      (node (ref "X4") (pin "8") (pinfunction "8_8") (pintype "passive"))
      (node (ref "X4") (pin "SH1") (pinfunction "PE1_SH1") (pintype "power_in"))
      (node (ref "X4") (pin "SH2") (pinfunction "PE2_SH2") (pintype "power_in"))
      (node (ref "X4") (pin "SH3") (pinfunction "PE3_SH3") (pintype "power_in"))
      (node (ref "X5") (pin "8") (pinfunction "8_8") (pintype "passive"))
      (node (ref "X5") (pin "SH1") (pinfunction "PE1_SH1") (pintype "power_in"))
      (node (ref "X5") (pin "SH2") (pinfunction "PE2_SH2") (pintype "power_in"))
      (node (ref "X5") (pin "SH3") (pinfunction "PE3_SH3") (pintype "power_in"))
      (node (ref "X6") (pin "8") (pinfunction "8_8") (pintype "passive"))
      (node (ref "X6") (pin "SH1") (pinfunction "PE1_SH1") (pintype "power_in"))
      (node (ref "X6") (pin "SH2") (pinfunction "PE2_SH2") (pintype "power_in"))
      (node (ref "X6") (pin "SH3") (pinfunction "PE3_SH3") (pintype "power_in"))
      (node (ref "X7") (pin "8") (pinfunction "8_8") (pintype "passive"))
      (node (ref "X7") (pin "SH1") (pinfunction "PE1_SH1") (pintype "power_in"))
      (node (ref "X7") (pin "SH2") (pinfunction "PE2_SH2") (pintype "power_in"))
      (node (ref "X7") (pin "SH3") (pinfunction "PE3_SH3") (pintype "power_in"))
      (node (ref "X8") (pin "8") (pinfunction "8_8") (pintype "passive"))
      (node (ref "X8") (pin "SH1") (pinfunction "PE1_SH1") (pintype "power_in"))
      (node (ref "X8") (pin "SH2") (pinfunction "PE2_SH2") (pintype "power_in"))
      (node (ref "X8") (pin "SH3") (pinfunction "PE3_SH3") (pintype "power_in"))
      (node (ref "X9") (pin "8") (pinfunction "8_8") (pintype "passive"))
      (node (ref "X9") (pin "SH1") (pinfunction "PE1_SH1") (pintype "power_in"))
      (node (ref "X9") (pin "SH2") (pinfunction "PE2_SH2") (pintype "power_in"))
      (node (ref "X9") (pin "SH3") (pinfunction "PE3_SH3") (pintype "power_in"))
    )
    (net (code "70") (name "unconnected-(U1-Pad33)") (class "Default")
      (node (ref "U1") (pin "33") (pinfunction "33_33") (pintype "passive"))
    )
    (net (code "71") (name "unconnected-(U1-Pad34)") (class "Default")
      (node (ref "U1") (pin "34") (pinfunction "34_34") (pintype "passive"))
    )
  )
)
